# H-Bridge-Discrete.net
KiCad netlist of a schematic drawn in EAGLE
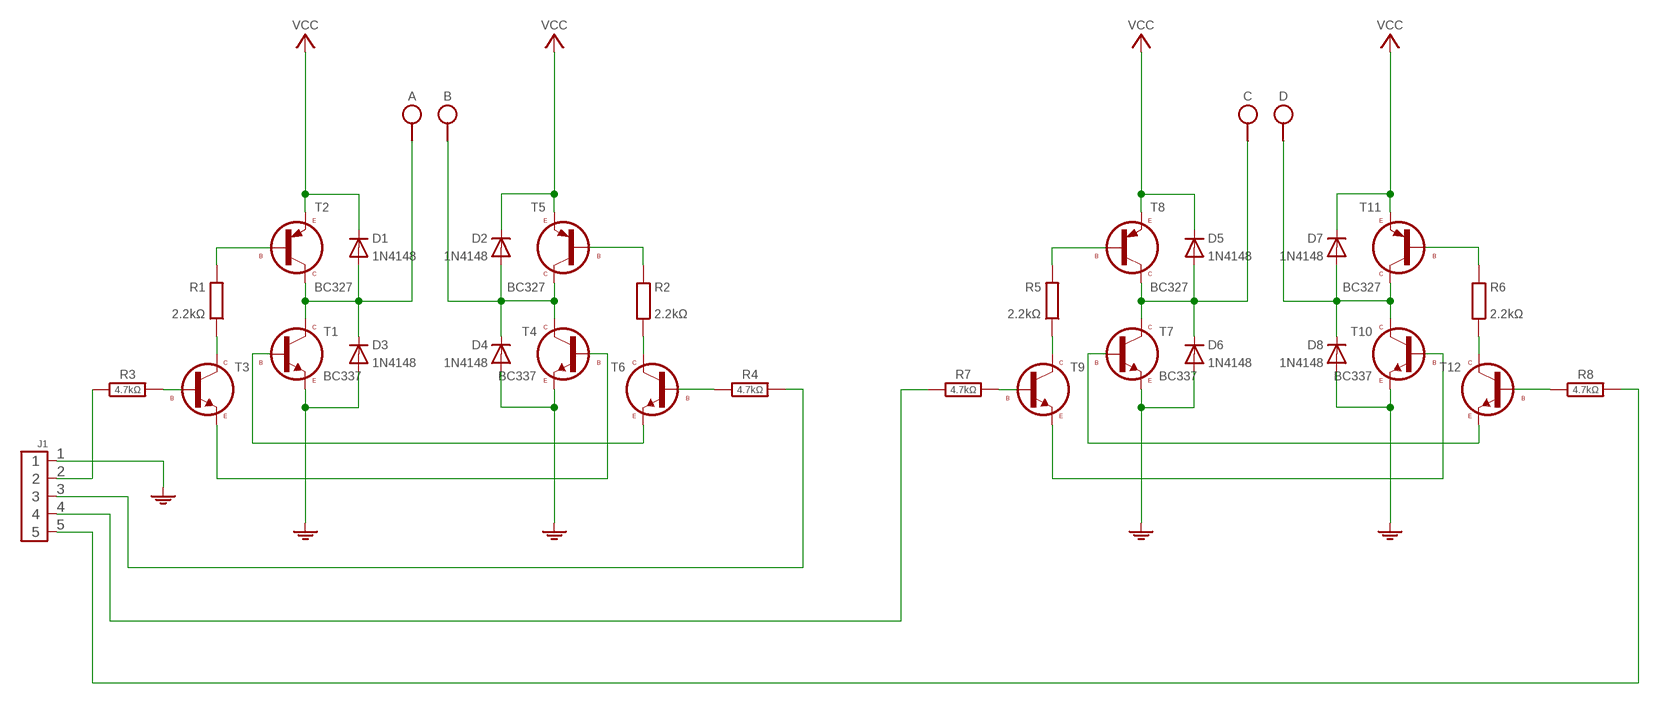
[diagram p0: schematic, sheet 1]

(export (version "E")
  (design (tool "Eeschema 10.0.6"))
  (components
    (comp (ref "A")
      (value "VPORT")
      (footprint "eagle-import:SPAD")
      (libsource (lib "eagle-import") (part "VPORT"))
    )
    (comp (ref "B")
      (value "VPORT")
      (footprint "eagle-import:SPAD")
      (libsource (lib "eagle-import") (part "VPORT"))
    )
    (comp (ref "C")
      (value "VPORT")
      (footprint "eagle-import:SPAD")
      (libsource (lib "eagle-import") (part "VPORT"))
    )
    (comp (ref "D")
      (value "VPORT")
      (footprint "eagle-import:SPAD")
      (libsource (lib "eagle-import") (part "VPORT"))
    )
    (comp (ref "D1")
      (value "1N4148")
      (footprint "eagle-import:DO7-5")
      (libsource (lib "eagle-import") (part "DIODE-7-5"))
    )
    (comp (ref "D2")
      (value "1N4148")
      (footprint "eagle-import:DO7-5")
      (libsource (lib "eagle-import") (part "DIODE-7-5"))
    )
    (comp (ref "D3")
      (value "1N4148")
      (footprint "eagle-import:DO7-5")
      (libsource (lib "eagle-import") (part "DIODE-7-5"))
    )
    (comp (ref "D4")
      (value "1N4148")
      (footprint "eagle-import:DO7-5")
      (libsource (lib "eagle-import") (part "DIODE-7-5"))
    )
    (comp (ref "D5")
      (value "1N4148")
      (footprint "eagle-import:DO7-5")
      (libsource (lib "eagle-import") (part "DIODE-7-5"))
    )
    (comp (ref "D6")
      (value "1N4148")
      (footprint "eagle-import:DO7-5")
      (libsource (lib "eagle-import") (part "DIODE-7-5"))
    )
    (comp (ref "D7")
      (value "1N4148")
      (footprint "eagle-import:DO7-5")
      (libsource (lib "eagle-import") (part "DIODE-7-5"))
    )
    (comp (ref "D8")
      (value "1N4148")
      (footprint "eagle-import:DO7-5")
      (libsource (lib "eagle-import") (part "DIODE-7-5"))
    )
    (comp (ref "J1")
      (value "CONN-5P-5P")
      (footprint "eagle-import:CONN-5P")
      (libsource (lib "eagle-import") (part "CONN-5P-5P"))
    )
    (comp (ref "R1")
      (value "2.2kΩ")
      (footprint "eagle-import:0204_10")
      (libsource (lib "eagle-import") (part "R0204/10"))
    )
    (comp (ref "R2")
      (value "2.2kΩ")
      (footprint "eagle-import:0204_2")
      (libsource (lib "eagle-import") (part "R0204/2"))
    )
    (comp (ref "R3")
      (value "4.7kΩ")
      (footprint "eagle-import:0204_10")
      (libsource (lib "eagle-import") (part "R-H0204/10"))
    )
    (comp (ref "R4")
      (value "4.7kΩ")
      (footprint "eagle-import:0204_10")
      (libsource (lib "eagle-import") (part "R-H0204/10"))
    )
    (comp (ref "R5")
      (value "2.2kΩ")
      (footprint "eagle-import:0204_10")
      (libsource (lib "eagle-import") (part "R0204/10"))
    )
    (comp (ref "R6")
      (value "2.2kΩ")
      (footprint "eagle-import:0204_10")
      (libsource (lib "eagle-import") (part "R0204/10"))
    )
    (comp (ref "R7")
      (value "4.7kΩ")
      (footprint "eagle-import:0204_10")
      (libsource (lib "eagle-import") (part "R-H0204/10"))
    )
    (comp (ref "R8")
      (value "4.7kΩ")
      (footprint "eagle-import:0204_10")
      (libsource (lib "eagle-import") (part "R-H0204/10"))
    )
    (comp (ref "S1")
      (value "VCC_GND-508-L")
      (footprint "eagle-import:PWR-508-L")
      (libsource (lib "eagle-import") (part "VCC_GND-508-L"))
    )
    (comp (ref "T1")
      (value "BC337")
      (footprint "eagle-import:TO92-CBE")
      (libsource (lib "eagle-import") (part "BC337CBE"))
    )
    (comp (ref "T2")
      (value "BC327")
      (footprint "eagle-import:TO92")
      (libsource (lib "eagle-import") (part "BC327"))
    )
    (comp (ref "T3")
      (value "BC547")
      (footprint "eagle-import:TO92")
      (libsource (lib "eagle-import") (part "BC547"))
    )
    (comp (ref "T4")
      (value "BC337")
      (footprint "eagle-import:TO92-CBE")
      (libsource (lib "eagle-import") (part "BC337CBE"))
    )
    (comp (ref "T5")
      (value "BC327")
      (footprint "eagle-import:TO92")
      (libsource (lib "eagle-import") (part "BC327"))
    )
    (comp (ref "T6")
      (value "BC547")
      (footprint "eagle-import:TO92")
      (libsource (lib "eagle-import") (part "BC547"))
    )
    (comp (ref "T7")
      (value "BC337")
      (footprint "eagle-import:TO92-CBE")
      (libsource (lib "eagle-import") (part "BC337CBE"))
    )
    (comp (ref "T8")
      (value "BC327")
      (footprint "eagle-import:TO92")
      (libsource (lib "eagle-import") (part "BC327"))
    )
    (comp (ref "T9")
      (value "BC547")
      (footprint "eagle-import:TO92")
      (libsource (lib "eagle-import") (part "BC547"))
    )
    (comp (ref "T10")
      (value "BC337")
      (footprint "eagle-import:TO92-CBE")
      (libsource (lib "eagle-import") (part "BC337CBE"))
    )
    (comp (ref "T11")
      (value "BC327")
      (footprint "eagle-import:TO92")
      (libsource (lib "eagle-import") (part "BC327"))
    )
    (comp (ref "T12")
      (value "BC547")
      (footprint "eagle-import:TO92")
      (libsource (lib "eagle-import") (part "BC547"))
    )
  )
  (nets
    (net (code "1") (name "GND") (class "Default")
      (node (ref "D3") (pin "A") (pinfunction "A_A") (pintype "passive"))
      (node (ref "D4") (pin "A") (pinfunction "A_A") (pintype "passive"))
      (node (ref "D6") (pin "A") (pinfunction "A_A") (pintype "passive"))
      (node (ref "D8") (pin "A") (pinfunction "A_A") (pintype "passive"))
      (node (ref "J1") (pin "1") (pinfunction "1_1") (pintype "bidirectional"))
      (node (ref "S1") (pin "1") (pinfunction "GND_1") (pintype "power_in"))
      (node (ref "T1") (pin "3") (pinfunction "E_3") (pintype "passive"))
      (node (ref "T10") (pin "3") (pinfunction "E_3") (pintype "passive"))
      (node (ref "T4") (pin "3") (pinfunction "E_3") (pintype "passive"))
      (node (ref "T7") (pin "3") (pinfunction "E_3") (pintype "passive"))
    )
    (net (code "2") (name "Net-(A-P$1)") (class "Default")
      (node (ref "A") (pin "1") (pinfunction "P$1_1") (pintype "passive"))
      (node (ref "D1") (pin "A") (pinfunction "A_A") (pintype "passive"))
      (node (ref "D3") (pin "C") (pinfunction "C_C") (pintype "passive"))
      (node (ref "T1") (pin "1") (pinfunction "C_1") (pintype "passive"))
      (node (ref "T2") (pin "1") (pinfunction "C_1") (pintype "passive"))
    )
    (net (code "3") (name "Net-(B-P$1)") (class "Default")
      (node (ref "B") (pin "1") (pinfunction "P$1_1") (pintype "passive"))
      (node (ref "D2") (pin "A") (pinfunction "A_A") (pintype "passive"))
      (node (ref "D4") (pin "C") (pinfunction "C_C") (pintype "passive"))
      (node (ref "T4") (pin "1") (pinfunction "C_1") (pintype "passive"))
      (node (ref "T5") (pin "1") (pinfunction "C_1") (pintype "passive"))
    )
    (net (code "4") (name "Net-(C-P$1)") (class "Default")
      (node (ref "C") (pin "1") (pinfunction "P$1_1") (pintype "passive"))
      (node (ref "D5") (pin "A") (pinfunction "A_A") (pintype "passive"))
      (node (ref "D6") (pin "C") (pinfunction "C_C") (pintype "passive"))
      (node (ref "T7") (pin "1") (pinfunction "C_1") (pintype "passive"))
      (node (ref "T8") (pin "1") (pinfunction "C_1") (pintype "passive"))
    )
    (net (code "5") (name "Net-(D-P$1)") (class "Default")
      (node (ref "D") (pin "1") (pinfunction "P$1_1") (pintype "passive"))
      (node (ref "D7") (pin "A") (pinfunction "A_A") (pintype "passive"))
      (node (ref "D8") (pin "C") (pinfunction "C_C") (pintype "passive"))
      (node (ref "T10") (pin "1") (pinfunction "C_1") (pintype "passive"))
      (node (ref "T11") (pin "1") (pinfunction "C_1") (pintype "passive"))
    )
    (net (code "6") (name "Net-(J1-Pad2)") (class "Default")
      (node (ref "J1") (pin "2") (pinfunction "2_2") (pintype "bidirectional"))
      (node (ref "R3") (pin "1") (pinfunction "1_1") (pintype "passive"))
    )
    (net (code "7") (name "Net-(J1-Pad3)") (class "Default")
      (node (ref "J1") (pin "3") (pinfunction "3_3") (pintype "bidirectional"))
      (node (ref "R4") (pin "2") (pinfunction "2_2") (pintype "passive"))
    )
    (net (code "8") (name "Net-(J1-Pad4)") (class "Default")
      (node (ref "J1") (pin "4") (pinfunction "4_4") (pintype "bidirectional"))
      (node (ref "R7") (pin "1") (pinfunction "1_1") (pintype "passive"))
    )
    (net (code "9") (name "Net-(J1-Pad5)") (class "Default")
      (node (ref "J1") (pin "5") (pinfunction "5_5") (pintype "bidirectional"))
      (node (ref "R8") (pin "2") (pinfunction "2_2") (pintype "passive"))
    )
    (net (code "10") (name "Net-(R1-1)") (class "Default")
      (node (ref "R1") (pin "2") (pinfunction "1_2") (pintype "passive"))
      (node (ref "T3") (pin "1") (pinfunction "C_1") (pintype "passive"))
    )
    (net (code "11") (name "Net-(R1-2)") (class "Default")
      (node (ref "R1") (pin "1") (pinfunction "2_1") (pintype "passive"))
      (node (ref "T2") (pin "2") (pinfunction "B_2") (pintype "passive"))
    )
    (net (code "12") (name "Net-(R2-1)") (class "Default")
      (node (ref "R2") (pin "2") (pinfunction "1_2") (pintype "passive"))
      (node (ref "T6") (pin "1") (pinfunction "C_1") (pintype "passive"))
    )
    (net (code "13") (name "Net-(R2-2)") (class "Default")
      (node (ref "R2") (pin "1") (pinfunction "2_1") (pintype "passive"))
      (node (ref "T5") (pin "2") (pinfunction "B_2") (pintype "passive"))
    )
    (net (code "14") (name "Net-(R5-1)") (class "Default")
      (node (ref "R5") (pin "2") (pinfunction "1_2") (pintype "passive"))
      (node (ref "T9") (pin "1") (pinfunction "C_1") (pintype "passive"))
    )
    (net (code "15") (name "Net-(R5-2)") (class "Default")
      (node (ref "R5") (pin "1") (pinfunction "2_1") (pintype "passive"))
      (node (ref "T8") (pin "2") (pinfunction "B_2") (pintype "passive"))
    )
    (net (code "16") (name "Net-(R6-1)") (class "Default")
      (node (ref "R6") (pin "2") (pinfunction "1_2") (pintype "passive"))
      (node (ref "T12") (pin "1") (pinfunction "C_1") (pintype "passive"))
    )
    (net (code "17") (name "Net-(R6-2)") (class "Default")
      (node (ref "R6") (pin "1") (pinfunction "2_1") (pintype "passive"))
      (node (ref "T11") (pin "2") (pinfunction "B_2") (pintype "passive"))
    )
    (net (code "18") (name "Net-(T1-B)") (class "Default")
      (node (ref "T1") (pin "2") (pinfunction "B_2") (pintype "passive"))
      (node (ref "T6") (pin "3") (pinfunction "E_3") (pintype "passive"))
    )
    (net (code "19") (name "Net-(T3-B)") (class "Default")
      (node (ref "R3") (pin "2") (pinfunction "2_2") (pintype "passive"))
      (node (ref "T3") (pin "2") (pinfunction "B_2") (pintype "passive"))
    )
    (net (code "20") (name "Net-(T3-E)") (class "Default")
      (node (ref "T3") (pin "3") (pinfunction "E_3") (pintype "passive"))
      (node (ref "T4") (pin "2") (pinfunction "B_2") (pintype "passive"))
    )
    (net (code "21") (name "Net-(T6-B)") (class "Default")
      (node (ref "R4") (pin "1") (pinfunction "1_1") (pintype "passive"))
      (node (ref "T6") (pin "2") (pinfunction "B_2") (pintype "passive"))
    )
    (net (code "22") (name "Net-(T9-B)") (class "Default")
      (node (ref "R7") (pin "2") (pinfunction "2_2") (pintype "passive"))
      (node (ref "T9") (pin "2") (pinfunction "B_2") (pintype "passive"))
    )
    (net (code "23") (name "Net-(T10-B)") (class "Default")
      (node (ref "T10") (pin "2") (pinfunction "B_2") (pintype "passive"))
      (node (ref "T9") (pin "3") (pinfunction "E_3") (pintype "passive"))
    )
    (net (code "24") (name "Net-(T12-B)") (class "Default")
      (node (ref "R8") (pin "1") (pinfunction "1_1") (pintype "passive"))
      (node (ref "T12") (pin "2") (pinfunction "B_2") (pintype "passive"))
    )
    (net (code "25") (name "Net-(T12-E)") (class "Default")
      (node (ref "T12") (pin "3") (pinfunction "E_3") (pintype "passive"))
      (node (ref "T7") (pin "2") (pinfunction "B_2") (pintype "passive"))
    )
    (net (code "26") (name "VCC") (class "Default")
      (node (ref "D1") (pin "C") (pinfunction "C_C") (pintype "passive"))
      (node (ref "D2") (pin "C") (pinfunction "C_C") (pintype "passive"))
      (node (ref "D5") (pin "C") (pinfunction "C_C") (pintype "passive"))
      (node (ref "D7") (pin "C") (pinfunction "C_C") (pintype "passive"))
      (node (ref "S1") (pin "2") (pinfunction "VCC_2") (pintype "power_in"))
      (node (ref "T11") (pin "3") (pinfunction "E_3") (pintype "passive"))
      (node (ref "T2") (pin "3") (pinfunction "E_3") (pintype "passive"))
      (node (ref "T5") (pin "3") (pinfunction "E_3") (pintype "passive"))
      (node (ref "T8") (pin "3") (pinfunction "E_3") (pintype "passive"))
    )
  )
)
